# sha2017_rev0_0_1_dev.net
KiCad netlist of a schematic drawn in EAGLE
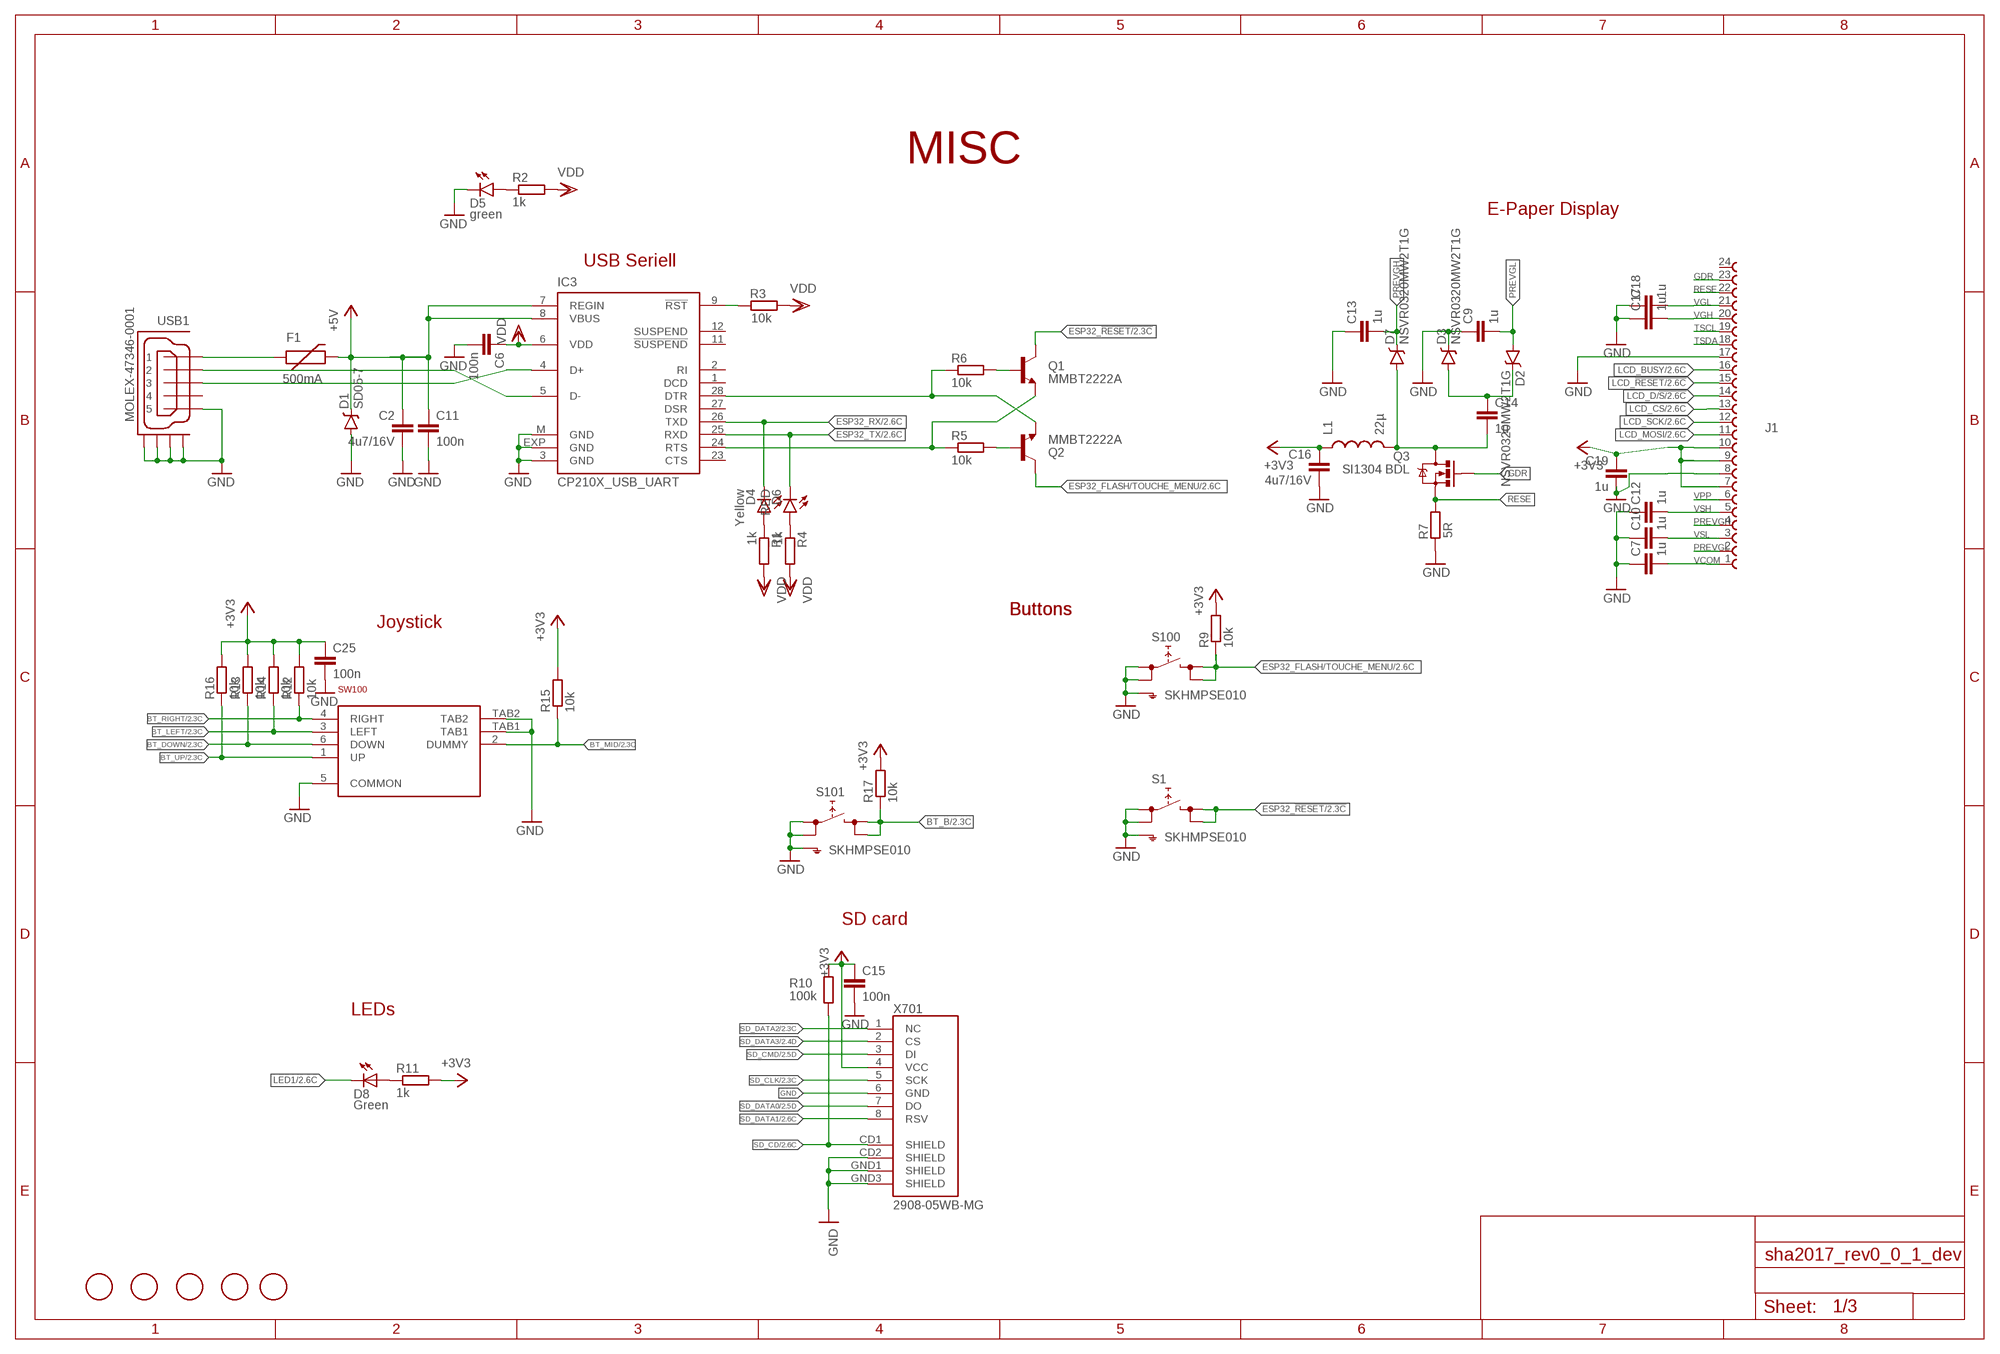
[diagram p0: schematic, sheet 1]
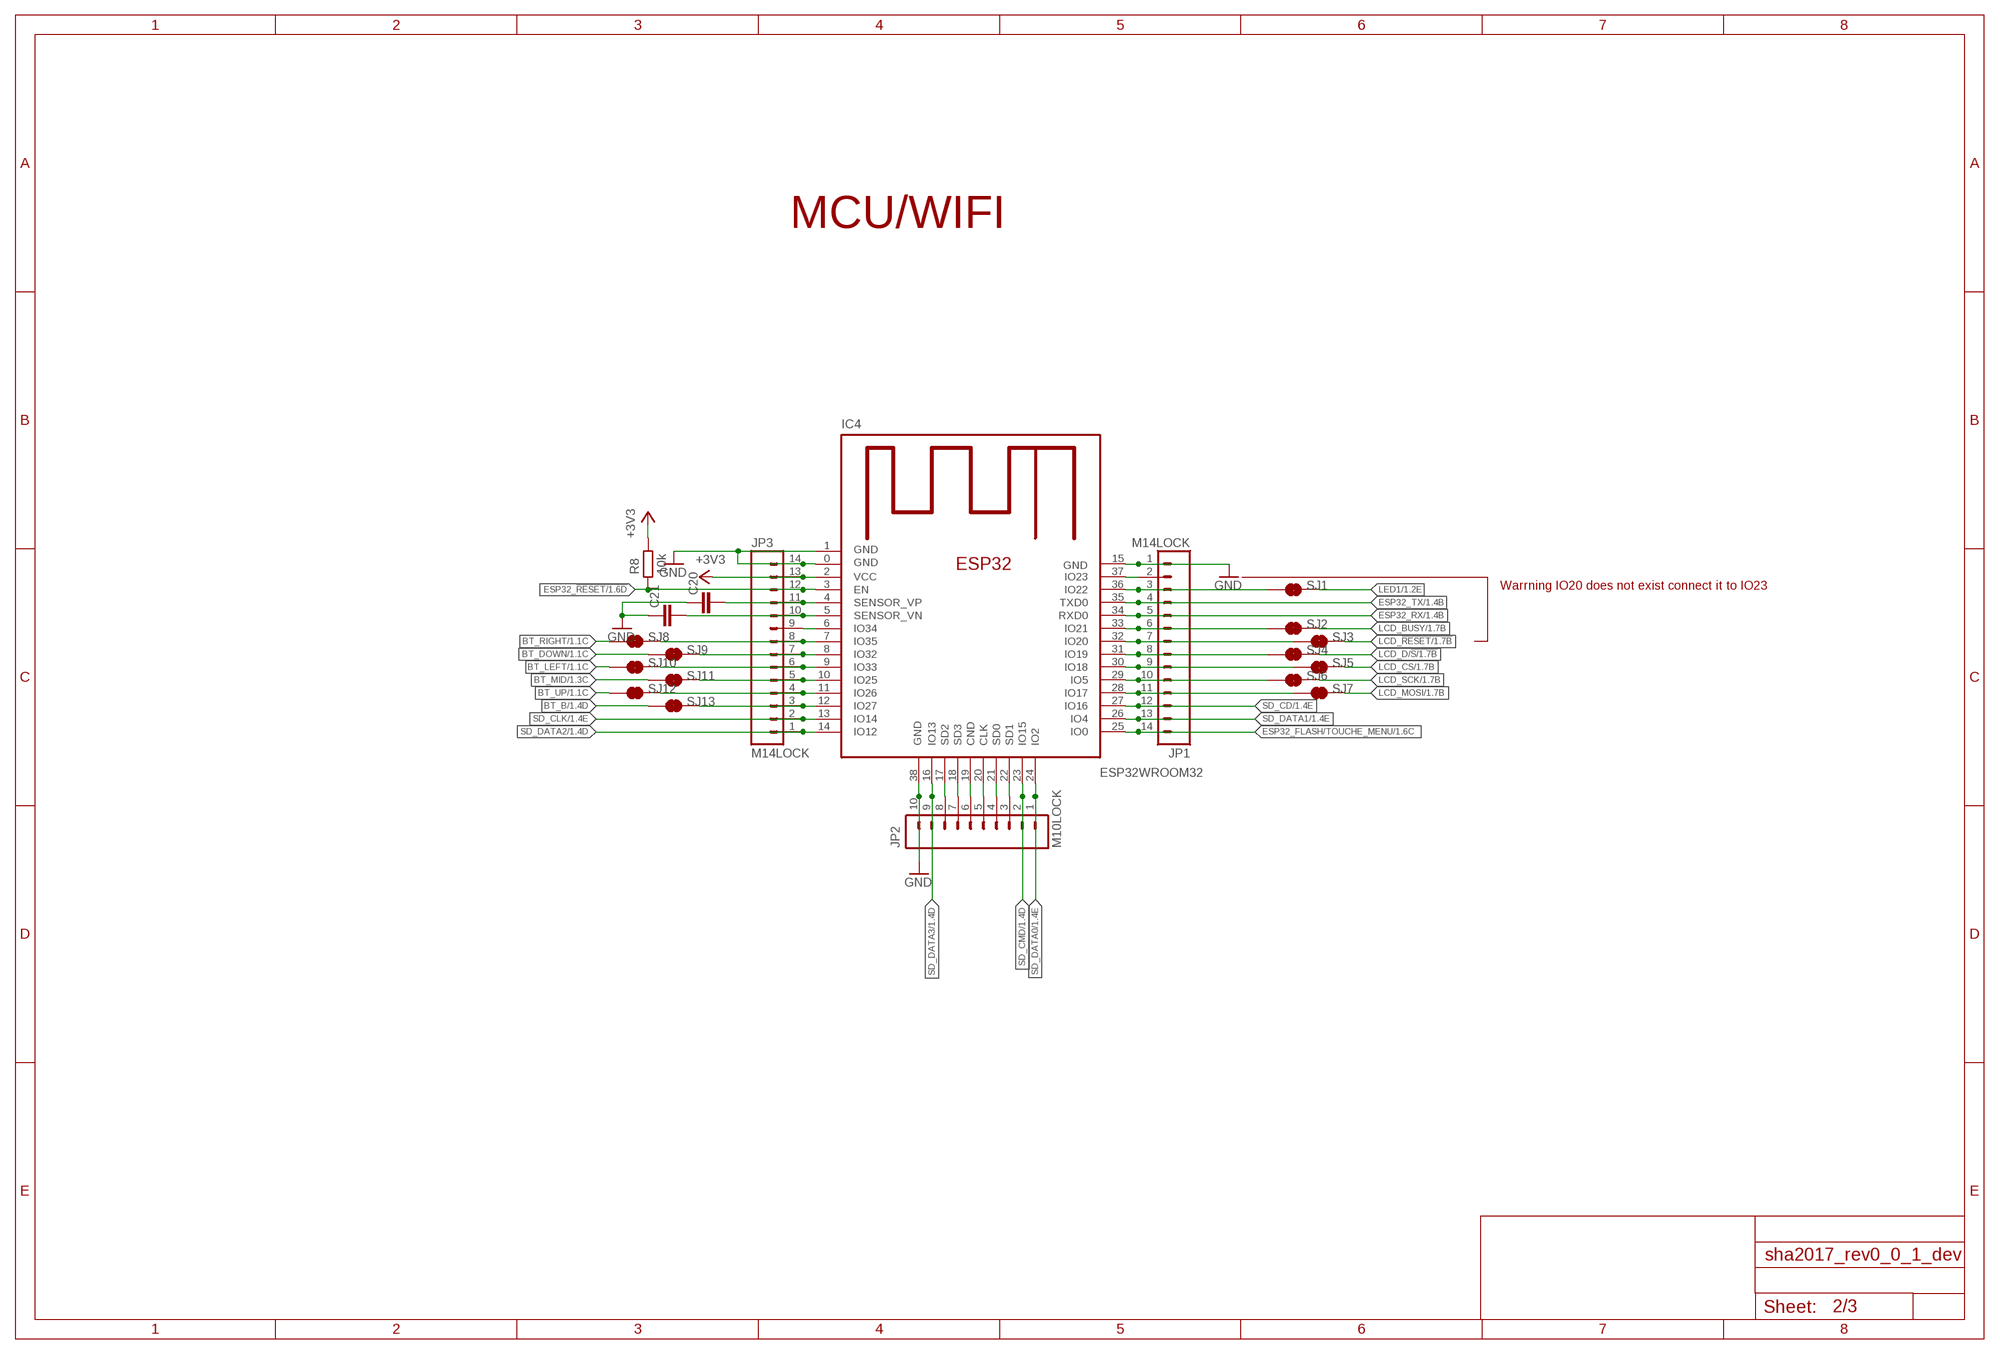
[diagram p1: schematic, sheet 2]
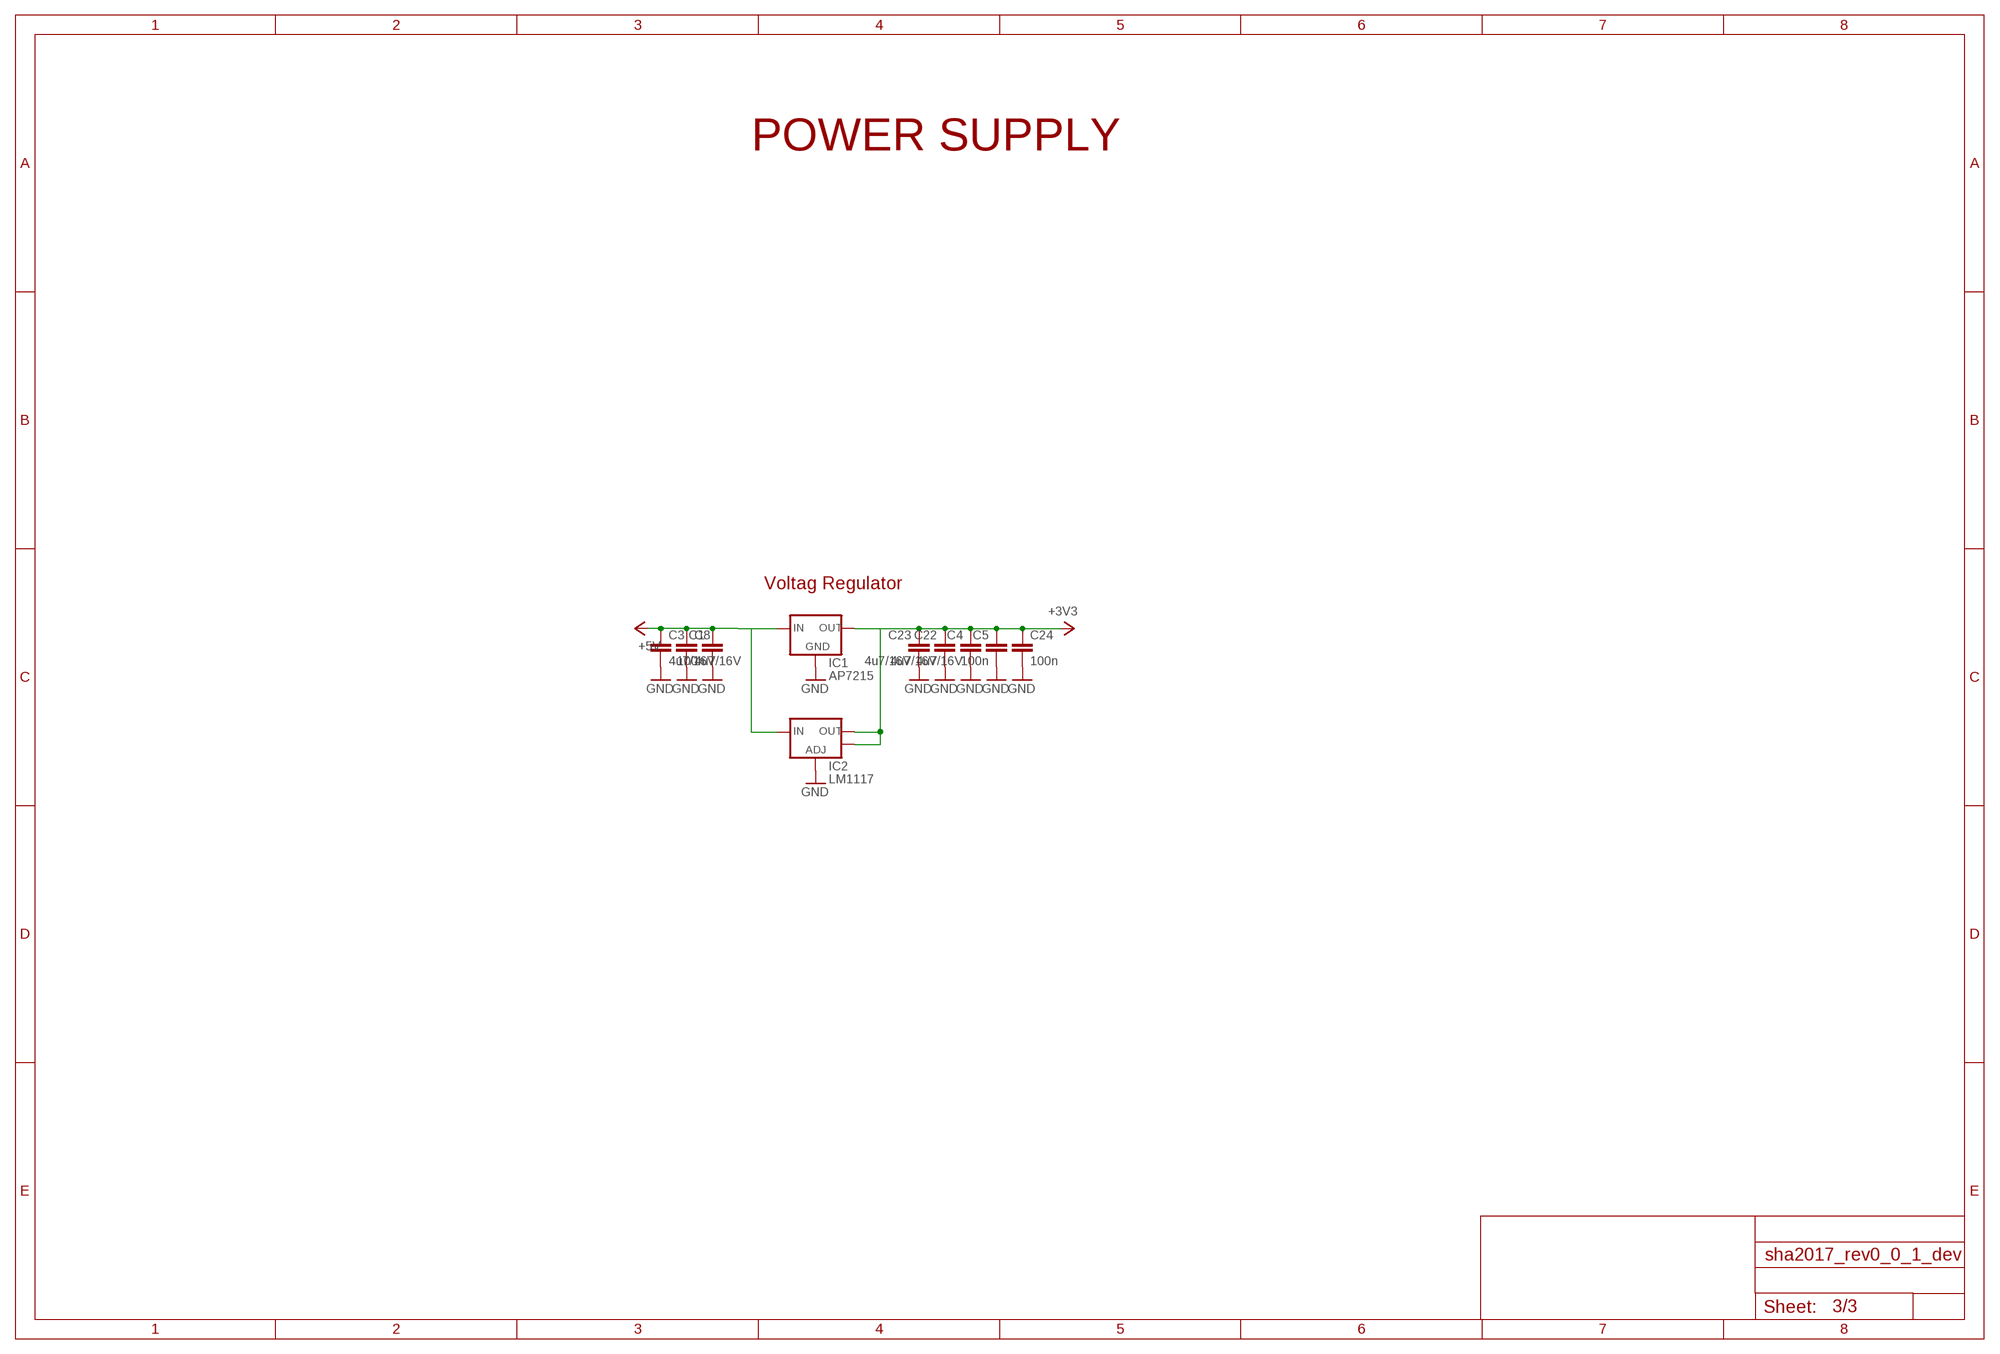
[diagram p2: schematic, sheet 3]

(export (version "E")
  (design (tool "Eeschema 10.0.6"))
  (components
    (comp (ref "C2")
      (value "4u7/16V")
      (footprint "eagle-import:C0805")
      (fields (field (name "PARTNO") "GRM21BR61C475KA88K"))
      (libsource (lib "eagle-import") (part "C-EUC0805"))
    )
    (comp (ref "C6")
      (value "100n")
      (footprint "eagle-import:C0603")
      (fields (field (name "PARTNO") "GRM188R71H104KA93D"))
      (libsource (lib "eagle-import") (part "C-EUC0603"))
    )
    (comp (ref "C7")
      (value "1u")
      (footprint "eagle-import:C0603")
      (fields (field (name "PARTNO") "GRM188R61E105KA12D"))
      (libsource (lib "eagle-import") (part "C-EUC0603"))
    )
    (comp (ref "C9")
      (value "1u")
      (footprint "eagle-import:C0603")
      (fields (field (name "PARTNO") "GRM188R61E105KA12D"))
      (libsource (lib "eagle-import") (part "C-EUC0603"))
    )
    (comp (ref "C10")
      (value "1u")
      (footprint "eagle-import:C0603")
      (fields (field (name "PARTNO") "GRM188R61E105KA12D"))
      (libsource (lib "eagle-import") (part "C-EUC0603"))
    )
    (comp (ref "C11")
      (value "100n")
      (footprint "eagle-import:C0603")
      (fields (field (name "PARTNO") "GRM188R71H104KA93D"))
      (libsource (lib "eagle-import") (part "C-EUC0603"))
    )
    (comp (ref "C12")
      (value "1u")
      (footprint "eagle-import:C0603")
      (fields (field (name "PARTNO") "GRM188R61E105KA12D"))
      (libsource (lib "eagle-import") (part "C-EUC0603"))
    )
    (comp (ref "C13")
      (value "1u")
      (footprint "eagle-import:C0603")
      (fields (field (name "PARTNO") "GRM188R61E105KA12D"))
      (libsource (lib "eagle-import") (part "C-EUC0603"))
    )
    (comp (ref "C14")
      (value "1u")
      (footprint "eagle-import:C0603")
      (fields (field (name "PARTNO") "GRM188R61E105KA12D"))
      (libsource (lib "eagle-import") (part "C-EUC0603"))
    )
    (comp (ref "C15")
      (value "100n")
      (footprint "eagle-import:C0603")
      (fields (field (name "PARTNO") "GRM188R71H104KA93D"))
      (libsource (lib "eagle-import") (part "C-EUC0603"))
    )
    (comp (ref "C16")
      (value "4u7/16V")
      (footprint "eagle-import:C0805")
      (fields (field (name "PARTNO") "GRM21BR61C475KA88K"))
      (libsource (lib "eagle-import") (part "C-EUC0805"))
    )
    (comp (ref "C17")
      (value "1u")
      (footprint "eagle-import:C0603")
      (fields (field (name "PARTNO") "GRM188R61E105KA12D"))
      (libsource (lib "eagle-import") (part "C-EUC0603"))
    )
    (comp (ref "C18")
      (value "1u")
      (footprint "eagle-import:C0603")
      (fields (field (name "PARTNO") "GRM188R61E105KA12D"))
      (libsource (lib "eagle-import") (part "C-EUC0603"))
    )
    (comp (ref "C19")
      (value "1u")
      (footprint "eagle-import:C0603")
      (fields (field (name "PARTNO") "GRM188R61E105KA12D"))
      (libsource (lib "eagle-import") (part "C-EUC0603"))
    )
    (comp (ref "C25")
      (value "100n")
      (footprint "eagle-import:C0603")
      (fields (field (name "PARTNO") "GRM188R71H104KA93D"))
      (libsource (lib "eagle-import") (part "C-EUC0603"))
    )
    (comp (ref "D1")
      (value "SD05-7")
      (footprint "eagle-import:SOD-323")
      (fields (field (name "PARTNO") "PMEG4005EJ,115"))
      (libsource (lib "eagle-import") (part "DIODE-SCHOTTKY-PMEG4005EJ"))
    )
    (comp (ref "D2")
      (value "NSVR0320MW2T1G")
      (footprint "eagle-import:SOD-323")
      (fields (field (name "PARTNO") "BAT20JFILM"))
      (libsource (lib "eagle-import") (part "BAT20JFILM"))
    )
    (comp (ref "D3")
      (value "NSVR0320MW2T1G")
      (footprint "eagle-import:SOD-323")
      (fields (field (name "PARTNO") "BAT20JFILM"))
      (libsource (lib "eagle-import") (part "BAT20JFILM"))
    )
    (comp (ref "D4")
      (value "Yellow")
      (footprint "eagle-import:LED-0603")
      (libsource (lib "eagle-import") (part "LED0603"))
    )
    (comp (ref "D5")
      (value "green")
      (footprint "eagle-import:LED-0603")
      (libsource (lib "eagle-import") (part "LED0603"))
    )
    (comp (ref "D6")
      (value "RED")
      (footprint "eagle-import:LED-0603")
      (libsource (lib "eagle-import") (part "LED0603"))
    )
    (comp (ref "D7")
      (value "NSVR0320MW2T1G")
      (footprint "eagle-import:SOD-323")
      (fields (field (name "PARTNO") "BAT20JFILM"))
      (libsource (lib "eagle-import") (part "BAT20JFILM"))
    )
    (comp (ref "D8")
      (value "Green")
      (footprint "eagle-import:SML1206")
      (fields (field (name "PARTNO") "156120VS75300"))
      (libsource (lib "eagle-import") (part "LEDSML1206"))
    )
    (comp (ref "F1")
      (value "500mA")
      (footprint "eagle-import:PTC-1206")
      (fields (field (name "PARTNO") "0ZCJ0025FF2E"))
      (libsource (lib "eagle-import") (part "PTCSMD"))
    )
    (comp (ref "FD1")
      (value "FIDUCIAL")
      (footprint "eagle-import:FIDUCIAL_1MM")
      (libsource (lib "eagle-import") (part "FIDUCIAL"))
    )
    (comp (ref "FD2")
      (value "FIDUCIAL")
      (footprint "eagle-import:FIDUCIAL_1MM")
      (libsource (lib "eagle-import") (part "FIDUCIAL"))
    )
    (comp (ref "FD3")
      (value "FIDUCIAL")
      (footprint "eagle-import:FIDUCIAL_1MM")
      (libsource (lib "eagle-import") (part "FIDUCIAL"))
    )
    (comp (ref "FD4")
      (value "FIDUCIAL")
      (footprint "eagle-import:FIDUCIAL_1MM")
      (libsource (lib "eagle-import") (part "FIDUCIAL"))
    )
    (comp (ref "FD5")
      (value "FIDUCIAL")
      (footprint "eagle-import:FIDUCIAL_1MM")
      (libsource (lib "eagle-import") (part "FIDUCIAL"))
    )
    (comp (ref "IC3")
      (value "CP210X_USB_UART")
      (footprint "eagle-import:MLP28")
      (fields (field (name "PARTNO") "CP2102-GMR"))
      (libsource (lib "eagle-import") (part "CP210X_USB_UART"))
    )
    (comp (ref "J1")
      (value "68712414022")
      (footprint "eagle-import:68712414022")
      (libsource (lib "eagle-import") (part "68712414022"))
    )
    (comp (ref "L1")
      (value "22µ")
      (footprint "eagle-import:1210")
      (fields (field (name "PARTNO") "NLCV32T-220K-EF"))
      (libsource (lib "eagle-import") (part "INDUCTOR1210"))
    )
    (comp (ref "Q1")
      (value "MMBT2222A")
      (footprint "eagle-import:SOT23-3")
      (fields (field (name "PARTNO") "BC817-25,215"))
      (libsource (lib "eagle-import") (part "TRANSISTOR_NPNMMBT2222A"))
    )
    (comp (ref "Q2")
      (value "MMBT2222A")
      (footprint "eagle-import:SOT23-3")
      (fields (field (name "PARTNO") "BC817-25,215"))
      (libsource (lib "eagle-import") (part "TRANSISTOR_NPNMMBT2222A"))
    )
    (comp (ref "Q3")
      (value "SI1304 BDL")
      (footprint "eagle-import:SOT323")
      (fields (field (name "PARTNO") "SI1308EDL-T1-GE3"))
      (libsource (lib "eagle-import") (part "MOSFET-NCHANNEL2N7002PW"))
    )
    (comp (ref "R1")
      (value "1k")
      (footprint "eagle-import:R0603")
      (fields (field (name "PARTNO") "ERJ-3GEYJ102V"))
      (libsource (lib "eagle-import") (part "R-EU_R0603"))
    )
    (comp (ref "R2")
      (value "1k")
      (footprint "eagle-import:R0603")
      (fields (field (name "PARTNO") "ERJ-3GEYJ102V"))
      (libsource (lib "eagle-import") (part "R-EU_R0603"))
    )
    (comp (ref "R3")
      (value "10k")
      (footprint "eagle-import:R0603")
      (fields (field (name "PARTNO") "ERJ-3GEYJ103V"))
      (libsource (lib "eagle-import") (part "R-EU_R0603"))
    )
    (comp (ref "R4")
      (value "1k")
      (footprint "eagle-import:R0603")
      (fields (field (name "PARTNO") "ERJ-3GEYJ102V"))
      (libsource (lib "eagle-import") (part "R-EU_R0603"))
    )
    (comp (ref "R5")
      (value "10k")
      (footprint "eagle-import:R0603")
      (fields (field (name "PARTNO") "ERJ-3GEYJ103V"))
      (libsource (lib "eagle-import") (part "R-EU_R0603"))
    )
    (comp (ref "R6")
      (value "10k")
      (footprint "eagle-import:R0603")
      (fields (field (name "PARTNO") "ERJ-3GEYJ103V"))
      (libsource (lib "eagle-import") (part "R-EU_R0603"))
    )
    (comp (ref "R7")
      (value "5R")
      (footprint "eagle-import:R0603-DASHES")
      (fields (field (name "PARTNO") "ERJ-3GEYJ5R1V"))
      (libsource (lib "eagle-import") (part "R0603-DASHES"))
    )
    (comp (ref "R9")
      (value "10k")
      (footprint "eagle-import:R0603")
      (fields (field (name "PARTNO") "ERJ-3GEYJ103V"))
      (libsource (lib "eagle-import") (part "R-EU_R0603"))
    )
    (comp (ref "R10")
      (value "100k")
      (footprint "eagle-import:R0603")
      (fields (field (name "PARTNO") "CRCW0603100KFKEA"))
      (libsource (lib "eagle-import") (part "R-EU_R0603"))
    )
    (comp (ref "R11")
      (value "1k")
      (footprint "eagle-import:R0603")
      (fields (field (name "PARTNO") "ERJ-3GEYJ102V"))
      (libsource (lib "eagle-import") (part "R-EU_R0603"))
    )
    (comp (ref "R12")
      (value "10k")
      (footprint "eagle-import:R0603")
      (fields (field (name "PARTNO") "ERJ-3GEYJ103V"))
      (libsource (lib "eagle-import") (part "R-EU_R0603"))
    )
    (comp (ref "R13")
      (value "10k")
      (footprint "eagle-import:R0603")
      (fields (field (name "PARTNO") "ERJ-3GEYJ103V"))
      (libsource (lib "eagle-import") (part "R-EU_R0603"))
    )
    (comp (ref "R14")
      (value "10k")
      (footprint "eagle-import:R0603")
      (fields (field (name "PARTNO") "ERJ-3GEYJ103V"))
      (libsource (lib "eagle-import") (part "R-EU_R0603"))
    )
    (comp (ref "R15")
      (value "10k")
      (footprint "eagle-import:R0603")
      (fields (field (name "PARTNO") "ERJ-3GEYJ103V"))
      (libsource (lib "eagle-import") (part "R-EU_R0603"))
    )
    (comp (ref "R16")
      (value "10k")
      (footprint "eagle-import:R0603")
      (fields (field (name "PARTNO") "ERJ-3GEYJ103V"))
      (libsource (lib "eagle-import") (part "R-EU_R0603"))
    )
    (comp (ref "R17")
      (value "10k")
      (footprint "eagle-import:R0603")
      (fields (field (name "PARTNO") "ERJ-3GEYJ103V"))
      (libsource (lib "eagle-import") (part "R-EU_R0603"))
    )
    (comp (ref "S1")
      (value "SKHMPSE010")
      (footprint "eagle-import:SKHMPXE010")
      (fields (field (name "PARTNO") "SKHMQME010"))
      (libsource (lib "eagle-import") (part "SKHMPE010S"))
    )
    (comp (ref "S100")
      (value "SKHMPSE010")
      (footprint "eagle-import:SKHMPXE010")
      (fields (field (name "PARTNO") "SKHMQME010"))
      (libsource (lib "eagle-import") (part "SKHMPE010S"))
    )
    (comp (ref "S101")
      (value "SKHMPSE010")
      (footprint "eagle-import:SKHMPXE010")
      (fields (field (name "PARTNO") "SKHMQME010"))
      (libsource (lib "eagle-import") (part "SKHMPE010S"))
    )
    (comp (ref "SW100")
      (value "MCMT5-F-V")
      (footprint "eagle-import:MCMT5-F-V")
      (fields (field (name "PARTNO") "SKRHAAE010"))
      (libsource (lib "eagle-import") (part "MCMT5-F-V"))
    )
    (comp (ref "USB1")
      (value "MOLEX-47346-0001")
      (footprint "eagle-import:MOLEX-47364-0001")
      (fields (field (name "PARTNO") "10118194-0001LF"))
      (libsource (lib "eagle-import") (part "MOLEX-47346-0001"))
    )
    (comp (ref "X701")
      (value "2908-05WB-MG")
      (footprint "eagle-import:MICRO-SD-SOCKET-PP")
      (libsource (lib "eagle-import") (part "2908-05WB-MG"))
    )
    (comp (ref "C1")
      (value "100n")
      (footprint "eagle-import:C0603")
      (fields (field (name "PARTNO") "GRM188R71H104KA93D"))
      (libsource (lib "eagle-import") (part "C-EUC0603"))
    )
    (comp (ref "C3")
      (value "4u7/16V")
      (footprint "eagle-import:C0805")
      (fields (field (name "PARTNO") "GRM21BR61C475KA88K"))
      (libsource (lib "eagle-import") (part "C-EUC0805"))
    )
    (comp (ref "C4")
      (value "4u7/16V")
      (footprint "eagle-import:C0805")
      (fields (field (name "PARTNO") "GRM21BR61C475KA88K"))
      (libsource (lib "eagle-import") (part "C-EUC0805"))
    )
    (comp (ref "C5")
      (value "100n")
      (footprint "eagle-import:C0603")
      (fields (field (name "PARTNO") "GRM188R71H104KA93D"))
      (libsource (lib "eagle-import") (part "C-EUC0603"))
    )
    (comp (ref "C8")
      (value "4u7/16V")
      (footprint "eagle-import:C0805")
      (fields (field (name "PARTNO") "GRM21BR61C475KA88K"))
      (libsource (lib "eagle-import") (part "C-EUC0805"))
    )
    (comp (ref "C22")
      (value "4u7/16V")
      (footprint "eagle-import:C0805")
      (fields (field (name "PARTNO") "GRM21BR61C475KA88K"))
      (libsource (lib "eagle-import") (part "C-EUC0805"))
    )
    (comp (ref "C23")
      (value "4u7/16V")
      (footprint "eagle-import:C0805")
      (fields (field (name "PARTNO") "GRM21BR61C475KA88K"))
      (libsource (lib "eagle-import") (part "C-EUC0805"))
    )
    (comp (ref "C24")
      (value "100n")
      (footprint "eagle-import:C0603")
      (fields (field (name "PARTNO") "GRM188R71H104KA93D"))
      (libsource (lib "eagle-import") (part "C-EUC0603"))
    )
    (comp (ref "IC1")
      (value "AP7215")
      (footprint "eagle-import:SOT89")
      (fields (field (name "PARTNO") "AP7215-33YG-13"))
      (libsource (lib "eagle-import") (part "AP7215"))
    )
    (comp (ref "IC2")
      (value "LM1117")
      (footprint "eagle-import:SOT223")
      (fields (field (name "PARTNO") "LM1117MPX-3.3/NOPB"))
      (libsource (lib "eagle-import") (part "V_REG_LM1117SOT223"))
    )
    (comp (ref "C20")
      (value "C-EUC0603")
      (footprint "eagle-import:C0603")
      (libsource (lib "eagle-import") (part "C-EUC0603"))
    )
    (comp (ref "C21")
      (value "C-EUC0603")
      (footprint "eagle-import:C0603")
      (libsource (lib "eagle-import") (part "C-EUC0603"))
    )
    (comp (ref "IC4")
      (value "ESP32WROOM32")
      (footprint "eagle-import:ESP32MOD")
      (libsource (lib "eagle-import") (part "ESP32WROOM32"))
    )
    (comp (ref "JP1")
      (value "M14LOCK")
      (footprint "eagle-import:1X14_LOCK")
      (libsource (lib "eagle-import") (part "M14LOCK"))
    )
    (comp (ref "JP2")
      (value "M10LOCK")
      (footprint "eagle-import:1X10_LOCK")
      (libsource (lib "eagle-import") (part "M10LOCK"))
    )
    (comp (ref "JP3")
      (value "M14LOCK")
      (footprint "eagle-import:1X14_LOCK")
      (libsource (lib "eagle-import") (part "M14LOCK"))
    )
    (comp (ref "R8")
      (value "10k")
      (footprint "eagle-import:R0603")
      (fields (field (name "PARTNO") "ERJ-3GEYJ103V"))
      (libsource (lib "eagle-import") (part "R-EU_R0603"))
    )
    (comp (ref "SJ1")
      (value "JUMPER-PAD-2-NC_BY_TRACE")
      (footprint "eagle-import:PAD-JUMPER-2-NC_BY_TRACE_YES_SILK")
      (libsource (lib "eagle-import") (part "JUMPER-PAD-2-NC_BY_TRACE"))
    )
    (comp (ref "SJ2")
      (value "JUMPER-PAD-2-NC_BY_TRACE")
      (footprint "eagle-import:PAD-JUMPER-2-NC_BY_TRACE_YES_SILK")
      (libsource (lib "eagle-import") (part "JUMPER-PAD-2-NC_BY_TRACE"))
    )
    (comp (ref "SJ3")
      (value "JUMPER-PAD-2-NC_BY_TRACE")
      (footprint "eagle-import:PAD-JUMPER-2-NC_BY_TRACE_YES_SILK")
      (libsource (lib "eagle-import") (part "JUMPER-PAD-2-NC_BY_TRACE"))
    )
    (comp (ref "SJ4")
      (value "JUMPER-PAD-2-NC_BY_TRACE")
      (footprint "eagle-import:PAD-JUMPER-2-NC_BY_TRACE_YES_SILK")
      (libsource (lib "eagle-import") (part "JUMPER-PAD-2-NC_BY_TRACE"))
    )
    (comp (ref "SJ5")
      (value "JUMPER-PAD-2-NC_BY_TRACE")
      (footprint "eagle-import:PAD-JUMPER-2-NC_BY_TRACE_YES_SILK")
      (libsource (lib "eagle-import") (part "JUMPER-PAD-2-NC_BY_TRACE"))
    )
    (comp (ref "SJ6")
      (value "JUMPER-PAD-2-NC_BY_TRACE")
      (footprint "eagle-import:PAD-JUMPER-2-NC_BY_TRACE_YES_SILK")
      (libsource (lib "eagle-import") (part "JUMPER-PAD-2-NC_BY_TRACE"))
    )
    (comp (ref "SJ7")
      (value "JUMPER-PAD-2-NC_BY_TRACE")
      (footprint "eagle-import:PAD-JUMPER-2-NC_BY_TRACE_YES_SILK")
      (libsource (lib "eagle-import") (part "JUMPER-PAD-2-NC_BY_TRACE"))
    )
    (comp (ref "SJ8")
      (value "JUMPER-PAD-2-NC_BY_TRACE")
      (footprint "eagle-import:PAD-JUMPER-2-NC_BY_TRACE_YES_SILK")
      (libsource (lib "eagle-import") (part "JUMPER-PAD-2-NC_BY_TRACE"))
    )
    (comp (ref "SJ9")
      (value "JUMPER-PAD-2-NC_BY_TRACE")
      (footprint "eagle-import:PAD-JUMPER-2-NC_BY_TRACE_YES_SILK")
      (libsource (lib "eagle-import") (part "JUMPER-PAD-2-NC_BY_TRACE"))
    )
    (comp (ref "SJ10")
      (value "JUMPER-PAD-2-NC_BY_TRACE")
      (footprint "eagle-import:PAD-JUMPER-2-NC_BY_TRACE_YES_SILK")
      (libsource (lib "eagle-import") (part "JUMPER-PAD-2-NC_BY_TRACE"))
    )
    (comp (ref "SJ11")
      (value "JUMPER-PAD-2-NC_BY_TRACE")
      (footprint "eagle-import:PAD-JUMPER-2-NC_BY_TRACE_YES_SILK")
      (libsource (lib "eagle-import") (part "JUMPER-PAD-2-NC_BY_TRACE"))
    )
    (comp (ref "SJ12")
      (value "JUMPER-PAD-2-NC_BY_TRACE")
      (footprint "eagle-import:PAD-JUMPER-2-NC_BY_TRACE_YES_SILK")
      (libsource (lib "eagle-import") (part "JUMPER-PAD-2-NC_BY_TRACE"))
    )
    (comp (ref "SJ13")
      (value "JUMPER-PAD-2-NC_BY_TRACE")
      (footprint "eagle-import:PAD-JUMPER-2-NC_BY_TRACE_YES_SILK")
      (libsource (lib "eagle-import") (part "JUMPER-PAD-2-NC_BY_TRACE"))
    )
  )
  (nets
    (net (code "1") (name "+3V3") (class "Default")
      (node (ref "C15") (pin "1") (pinfunction "1_1") (pintype "passive"))
      (node (ref "C16") (pin "1") (pinfunction "1_1") (pintype "passive"))
      (node (ref "C19") (pin "1") (pinfunction "1_1") (pintype "passive"))
      (node (ref "C22") (pin "1") (pinfunction "1_1") (pintype "passive"))
      (node (ref "C23") (pin "1") (pinfunction "1_1") (pintype "passive"))
      (node (ref "C24") (pin "1") (pinfunction "1_1") (pintype "passive"))
      (node (ref "C25") (pin "1") (pinfunction "1_1") (pintype "passive"))
      (node (ref "C4") (pin "1") (pinfunction "1_1") (pintype "passive"))
      (node (ref "C5") (pin "1") (pinfunction "1_1") (pintype "passive"))
      (node (ref "IC1") (pin "3") (pinfunction "OUT_3") (pintype "passive"))
      (node (ref "IC2") (pin "2") (pinfunction "OUT_2") (pintype "output"))
      (node (ref "IC2") (pin "4") (pinfunction "OUT_4") (pintype "output"))
      (node (ref "IC4") (pin "2") (pinfunction "VCC_2") (pintype "power_in"))
      (node (ref "J1") (pin "10") (pinfunction "10_10") (pintype "passive"))
      (node (ref "J1") (pin "7") (pinfunction "7_7") (pintype "passive"))
      (node (ref "J1") (pin "9") (pinfunction "9_9") (pintype "passive"))
      (node (ref "JP3") (pin "13") (pinfunction "13_13") (pintype "passive"))
      (node (ref "L1") (pin "1") (pinfunction "1_1") (pintype "passive"))
      (node (ref "R10") (pin "1") (pinfunction "1_1") (pintype "passive"))
      (node (ref "R11") (pin "2") (pinfunction "2_2") (pintype "passive"))
      (node (ref "R12") (pin "2") (pinfunction "2_2") (pintype "passive"))
      (node (ref "R13") (pin "2") (pinfunction "2_2") (pintype "passive"))
      (node (ref "R14") (pin "2") (pinfunction "2_2") (pintype "passive"))
      (node (ref "R15") (pin "2") (pinfunction "2_2") (pintype "passive"))
      (node (ref "R16") (pin "2") (pinfunction "2_2") (pintype "passive"))
      (node (ref "R17") (pin "2") (pinfunction "2_2") (pintype "passive"))
      (node (ref "R8") (pin "1") (pinfunction "1_1") (pintype "passive"))
      (node (ref "R9") (pin "2") (pinfunction "2_2") (pintype "passive"))
      (node (ref "X701") (pin "4") (pinfunction "VCC_4") (pintype "bidirectional"))
    )
    (net (code "2") (name "+5V") (class "Default")
      (node (ref "C1") (pin "1") (pinfunction "1_1") (pintype "passive"))
      (node (ref "C11") (pin "1") (pinfunction "1_1") (pintype "passive"))
      (node (ref "C2") (pin "1") (pinfunction "1_1") (pintype "passive"))
      (node (ref "C3") (pin "1") (pinfunction "1_1") (pintype "passive"))
      (node (ref "C8") (pin "1") (pinfunction "1_1") (pintype "passive"))
      (node (ref "D1") (pin "C") (pinfunction "C_C") (pintype "passive"))
      (node (ref "F1") (pin "2") (pinfunction "2_2") (pintype "bidirectional"))
      (node (ref "IC1") (pin "2") (pinfunction "IN_2") (pintype "input"))
      (node (ref "IC1") (pin "2@") (pinfunction "IN_2@") (pintype "input"))
      (node (ref "IC2") (pin "3") (pinfunction "IN_3") (pintype "input"))
      (node (ref "IC3") (pin "7") (pinfunction "REGIN_7") (pintype "passive"))
      (node (ref "IC3") (pin "8") (pinfunction "VBUS_8") (pintype "input"))
    )
    (net (code "3") (name "BT_B") (class "Default")
      (node (ref "R17") (pin "1") (pinfunction "1_1") (pintype "passive"))
      (node (ref "S101") (pin "3") (pinfunction "2.1_3") (pintype "passive"))
      (node (ref "S101") (pin "4") (pinfunction "2.2_4") (pintype "passive"))
      (node (ref "SJ13") (pin "1") (pinfunction "1_1") (pintype "passive"))
    )
    (net (code "4") (name "BT_DOWN") (class "Default")
      (node (ref "R13") (pin "1") (pinfunction "1_1") (pintype "passive"))
      (node (ref "SJ9") (pin "1") (pinfunction "1_1") (pintype "passive"))
      (node (ref "SW100") (pin "6") (pinfunction "DOWN_6") (pintype "bidirectional"))
    )
    (net (code "5") (name "BT_LEFT") (class "Default")
      (node (ref "R14") (pin "1") (pinfunction "1_1") (pintype "passive"))
      (node (ref "SJ10") (pin "1") (pinfunction "1_1") (pintype "passive"))
      (node (ref "SW100") (pin "3") (pinfunction "LEFT_3") (pintype "bidirectional"))
    )
    (net (code "6") (name "BT_MID") (class "Default")
      (node (ref "R15") (pin "1") (pinfunction "1_1") (pintype "passive"))
      (node (ref "SJ11") (pin "1") (pinfunction "1_1") (pintype "passive"))
      (node (ref "SW100") (pin "2") (pinfunction "DUMMY_2") (pintype "bidirectional"))
    )
    (net (code "7") (name "BT_RIGHT") (class "Default")
      (node (ref "R12") (pin "1") (pinfunction "1_1") (pintype "passive"))
      (node (ref "SJ8") (pin "1") (pinfunction "1_1") (pintype "passive"))
      (node (ref "SW100") (pin "4") (pinfunction "RIGHT_4") (pintype "bidirectional"))
    )
    (net (code "8") (name "BT_UP") (class "Default")
      (node (ref "R16") (pin "1") (pinfunction "1_1") (pintype "passive"))
      (node (ref "SJ12") (pin "1") (pinfunction "1_1") (pintype "passive"))
      (node (ref "SW100") (pin "1") (pinfunction "UP_1") (pintype "bidirectional"))
    )
    (net (code "9") (name "ESP32_FLASH{slash}TOUCHE_MENU") (class "Default")
      (node (ref "IC4") (pin "25") (pinfunction "IO0_25") (pintype "bidirectional"))
      (node (ref "JP1") (pin "14") (pinfunction "14_14") (pintype "passive"))
      (node (ref "Q2") (pin "3") (pinfunction "C_3") (pintype "passive"))
      (node (ref "R9") (pin "1") (pinfunction "1_1") (pintype "passive"))
      (node (ref "S100") (pin "3") (pinfunction "2.1_3") (pintype "passive"))
      (node (ref "S100") (pin "4") (pinfunction "2.2_4") (pintype "passive"))
    )
    (net (code "10") (name "ESP32_RX") (class "Default")
      (node (ref "D4") (pin "C") (pinfunction "C_C") (pintype "passive"))
      (node (ref "IC3") (pin "26") (pinfunction "TXD_26") (pintype "output"))
      (node (ref "IC4") (pin "34") (pinfunction "RXD0_34") (pintype "bidirectional"))
      (node (ref "JP1") (pin "5") (pinfunction "5_5") (pintype "passive"))
    )
    (net (code "11") (name "ESP32_TX") (class "Default")
      (node (ref "D6") (pin "C") (pinfunction "C_C") (pintype "passive"))
      (node (ref "IC3") (pin "25") (pinfunction "RXD_25") (pintype "input"))
      (node (ref "IC4") (pin "35") (pinfunction "TXD0_35") (pintype "bidirectional"))
      (node (ref "JP1") (pin "4") (pinfunction "4_4") (pintype "passive"))
    )
    (net (code "12") (name "ESP32_~{RESET}") (class "Default")
      (node (ref "IC4") (pin "3") (pinfunction "EN_3") (pintype "bidirectional"))
      (node (ref "JP3") (pin "12") (pinfunction "12_12") (pintype "passive"))
      (node (ref "Q1") (pin "3") (pinfunction "C_3") (pintype "passive"))
      (node (ref "R8") (pin "2") (pinfunction "2_2") (pintype "passive"))
      (node (ref "S1") (pin "3") (pinfunction "2.1_3") (pintype "passive"))
      (node (ref "S1") (pin "4") (pinfunction "2.2_4") (pintype "passive"))
    )
    (net (code "13") (name "GDR") (class "Default")
      (node (ref "J1") (pin "23") (pinfunction "23_23") (pintype "passive"))
      (node (ref "Q3") (pin "1") (pinfunction "G_1") (pintype "passive"))
    )
    (net (code "14") (name "GND") (class "Default")
      (node (ref "C1") (pin "2") (pinfunction "2_2") (pintype "passive"))
      (node (ref "C10") (pin "1") (pinfunction "1_1") (pintype "passive"))
      (node (ref "C11") (pin "2") (pinfunction "2_2") (pintype "passive"))
      (node (ref "C12") (pin "1") (pinfunction "1_1") (pintype "passive"))
      (node (ref "C13") (pin "1") (pinfunction "1_1") (pintype "passive"))
      (node (ref "C15") (pin "2") (pinfunction "2_2") (pintype "passive"))
      (node (ref "C16") (pin "2") (pinfunction "2_2") (pintype "passive"))
      (node (ref "C17") (pin "1") (pinfunction "1_1") (pintype "passive"))
      (node (ref "C18") (pin "1") (pinfunction "1_1") (pintype "passive"))
      (node (ref "C19") (pin "2") (pinfunction "2_2") (pintype "passive"))
      (node (ref "C2") (pin "2") (pinfunction "2_2") (pintype "passive"))
      (node (ref "C20") (pin "1") (pinfunction "1_1") (pintype "passive"))
      (node (ref "C21") (pin "1") (pinfunction "1_1") (pintype "passive"))
      (node (ref "C22") (pin "2") (pinfunction "2_2") (pintype "passive"))
      (node (ref "C23") (pin "2") (pinfunction "2_2") (pintype "passive"))
      (node (ref "C24") (pin "2") (pinfunction "2_2") (pintype "passive"))
      (node (ref "C25") (pin "2") (pinfunction "2_2") (pintype "passive"))
      (node (ref "C3") (pin "2") (pinfunction "2_2") (pintype "passive"))
      (node (ref "C4") (pin "2") (pinfunction "2_2") (pintype "passive"))
      (node (ref "C5") (pin "2") (pinfunction "2_2") (pintype "passive"))
      (node (ref "C6") (pin "2") (pinfunction "2_2") (pintype "passive"))
      (node (ref "C7") (pin "1") (pinfunction "1_1") (pintype "passive"))
      (node (ref "C8") (pin "2") (pinfunction "2_2") (pintype "passive"))
      (node (ref "C9") (pin "1") (pinfunction "1_1") (pintype "passive"))
      (node (ref "D1") (pin "A") (pinfunction "A_A") (pintype "passive"))
      (node (ref "D3") (pin "C") (pinfunction "C_C") (pintype "passive"))
      (node (ref "D5") (pin "C") (pinfunction "C_C") (pintype "passive"))
      (node (ref "IC1") (pin "1") (pinfunction "GND_1") (pintype "input"))
      (node (ref "IC2") (pin "1") (pinfunction "ADJ_1") (pintype "input"))
      (node (ref "IC3") (pin "3") (pinfunction "GND_3") (pintype "power_in"))
      (node (ref "IC3") (pin "EXP") (pinfunction "GND_EXP") (pintype "power_in"))
      (node (ref "IC3") (pin "M") (pinfunction "GND_M") (pintype "power_in"))
      (node (ref "IC4") (pin "0") (pinfunction "GND_0") (pintype "power_in"))
      (node (ref "IC4") (pin "1") (pinfunction "GND_1") (pintype "power_in"))
      (node (ref "IC4") (pin "15") (pinfunction "GND_15") (pintype "power_in"))
      (node (ref "IC4") (pin "38") (pinfunction "GND_38") (pintype "power_in"))
      (node (ref "J1") (pin "17") (pinfunction "17_17") (pintype "passive"))
      (node (ref "J1") (pin "8") (pinfunction "8_8") (pintype "passive"))
      (node (ref "JP1") (pin "1") (pinfunction "1_1") (pintype "passive"))
      (node (ref "JP2") (pin "10") (pinfunction "10_10") (pintype "passive"))
      (node (ref "JP3") (pin "14") (pinfunction "14_14") (pintype "passive"))
      (node (ref "R7") (pin "2") (pinfunction "2_2") (pintype "passive"))
      (node (ref "S1") (pin "1") (pinfunction "1.1_1") (pintype "passive"))
      (node (ref "S1") (pin "2") (pinfunction "1.2_2") (pintype "passive"))
      (node (ref "S1") (pin "5") (pinfunction "SH_5") (pintype "passive"))
      (node (ref "S100") (pin "1") (pinfunction "1.1_1") (pintype "passive"))
      (node (ref "S100") (pin "2") (pinfunction "1.2_2") (pintype "passive"))
      (node (ref "S100") (pin "5") (pinfunction "SH_5") (pintype "passive"))
      (node (ref "S101") (pin "1") (pinfunction "1.1_1") (pintype "passive"))
      (node (ref "S101") (pin "2") (pinfunction "1.2_2") (pintype "passive"))
      (node (ref "S101") (pin "5") (pinfunction "SH_5") (pintype "passive"))
      (node (ref "SW100") (pin "5") (pinfunction "COMMON_5") (pintype "bidirectional"))
      (node (ref "SW100") (pin "TAB1") (pinfunction "TAB1_TAB1") (pintype "bidirectional"))
      (node (ref "SW100") (pin "TAB2") (pinfunction "TAB2_TAB2") (pintype "bidirectional"))
      (node (ref "USB1") (pin "5") (pinfunction "5_5") (pintype "input"))
      (node (ref "USB1") (pin "GND1") (pinfunction "GND1_GND1") (pintype "bidirectional"))
      (node (ref "USB1") (pin "GND2") (pinfunction "GND2_GND2") (pintype "bidirectional"))
      (node (ref "USB1") (pin "GND3") (pinfunction "GND3_GND3") (pintype "bidirectional"))
      (node (ref "USB1") (pin "GND4") (pinfunction "GND4_GND4") (pintype "bidirectional"))
      (node (ref "X701") (pin "6") (pinfunction "GND_6") (pintype "bidirectional"))
      (node (ref "X701") (pin "CD2") (pinfunction "SHIELD_CD2") (pintype "bidirectional"))
      (node (ref "X701") (pin "GND1") (pinfunction "SHIELD_GND1") (pintype "bidirectional"))
      (node (ref "X701") (pin "GND3") (pinfunction "SHIELD_GND3") (pintype "bidirectional"))
    )
    (net (code "15") (name "LCD_BUSY") (class "Default")
      (node (ref "J1") (pin "16") (pinfunction "16_16") (pintype "passive"))
      (node (ref "SJ2") (pin "2") (pinfunction "2_2") (pintype "passive"))
    )
    (net (code "16") (name "LCD_CS") (class "Default")
      (node (ref "J1") (pin "13") (pinfunction "13_13") (pintype "passive"))
      (node (ref "SJ5") (pin "2") (pinfunction "2_2") (pintype "passive"))
    )
    (net (code "17") (name "LCD_D{slash}~{S}") (class "Default")
      (node (ref "J1") (pin "14") (pinfunction "14_14") (pintype "passive"))
      (node (ref "SJ4") (pin "2") (pinfunction "2_2") (pintype "passive"))
    )
    (net (code "18") (name "LCD_MOSI") (class "Default")
      (node (ref "J1") (pin "11") (pinfunction "11_11") (pintype "passive"))
      (node (ref "SJ7") (pin "2") (pinfunction "2_2") (pintype "passive"))
    )
    (net (code "19") (name "LCD_SCK") (class "Default")
      (node (ref "J1") (pin "12") (pinfunction "12_12") (pintype "passive"))
      (node (ref "SJ6") (pin "2") (pinfunction "2_2") (pintype "passive"))
    )
    (net (code "20") (name "LCD_~{RESET}") (class "Default")
      (node (ref "J1") (pin "15") (pinfunction "15_15") (pintype "passive"))
      (node (ref "SJ3") (pin "2") (pinfunction "2_2") (pintype "passive"))
    )
    (net (code "21") (name "LED1") (class "Default")
      (node (ref "D8") (pin "C") (pinfunction "C_C") (pintype "passive"))
      (node (ref "SJ1") (pin "2") (pinfunction "2_2") (pintype "passive"))
    )
    (net (code "22") (name "Net-(C14-Pad1)") (class "Default")
      (node (ref "C14") (pin "1") (pinfunction "1_1") (pintype "passive"))
      (node (ref "D2") (pin "C") (pinfunction "C_C") (pintype "passive"))
      (node (ref "D3") (pin "A") (pinfunction "A_A") (pintype "passive"))
    )
    (net (code "23") (name "Net-(D4-PadA)") (class "Default")
      (node (ref "D4") (pin "A") (pinfunction "A_A") (pintype "passive"))
      (node (ref "R1") (pin "1") (pinfunction "1_1") (pintype "passive"))
    )
    (net (code "24") (name "Net-(D5-PadA)") (class "Default")
      (node (ref "D5") (pin "A") (pinfunction "A_A") (pintype "passive"))
      (node (ref "R2") (pin "1") (pinfunction "1_1") (pintype "passive"))
    )
    (net (code "25") (name "Net-(D6-PadA)") (class "Default")
      (node (ref "D6") (pin "A") (pinfunction "A_A") (pintype "passive"))
      (node (ref "R4") (pin "1") (pinfunction "1_1") (pintype "passive"))
    )
    (net (code "26") (name "Net-(D8-PadA)") (class "Default")
      (node (ref "D8") (pin "A") (pinfunction "A_A") (pintype "passive"))
      (node (ref "R11") (pin "1") (pinfunction "1_1") (pintype "passive"))
    )
    (net (code "27") (name "Net-(F1-Pad1)") (class "Default")
      (node (ref "F1") (pin "1") (pinfunction "1_1") (pintype "bidirectional"))
      (node (ref "USB1") (pin "1") (pinfunction "1_1") (pintype "input"))
    )
    (net (code "28") (name "Net-(IC3-D+)") (class "Default")
      (node (ref "IC3") (pin "4") (pinfunction "D+_4") (pintype "bidirectional"))
      (node (ref "USB1") (pin "3") (pinfunction "3_3") (pintype "input"))
    )
    (net (code "29") (name "Net-(IC3-D-)") (class "Default")
      (node (ref "IC3") (pin "5") (pinfunction "D-_5") (pintype "bidirectional"))
      (node (ref "USB1") (pin "2") (pinfunction "2_2") (pintype "input"))
    )
    (net (code "30") (name "Net-(IC3-DTR)") (class "Default")
      (node (ref "IC3") (pin "28") (pinfunction "DTR_28") (pintype "output"))
      (node (ref "Q2") (pin "2") (pinfunction "E_2") (pintype "passive"))
      (node (ref "R6") (pin "1") (pinfunction "1_1") (pintype "passive"))
    )
    (net (code "31") (name "Net-(IC3-RTS)") (class "Default")
      (node (ref "IC3") (pin "24") (pinfunction "RTS_24") (pintype "output"))
      (node (ref "Q1") (pin "2") (pinfunction "E_2") (pintype "passive"))
      (node (ref "R5") (pin "1") (pinfunction "1_1") (pintype "passive"))
    )
    (net (code "32") (name "Net-(IC3-~{RST})") (class "Default")
      (node (ref "IC3") (pin "9") (pinfunction "~{RST}_9") (pintype "bidirectional"))
      (node (ref "R3") (pin "2") (pinfunction "2_2") (pintype "passive"))
    )
    (net (code "33") (name "Net-(IC4-CLK)") (class "Default")
      (node (ref "IC4") (pin "20") (pinfunction "CLK_20") (pintype "bidirectional"))
      (node (ref "JP2") (pin "5") (pinfunction "5_5") (pintype "passive"))
    )
    (net (code "34") (name "Net-(IC4-CND)") (class "Default")
      (node (ref "IC4") (pin "19") (pinfunction "CND_19") (pintype "bidirectional"))
      (node (ref "JP2") (pin "6") (pinfunction "6_6") (pintype "passive"))
    )
    (net (code "35") (name "Net-(IC4-IO5)") (class "Default")
      (node (ref "IC4") (pin "29") (pinfunction "IO5_29") (pintype "bidirectional"))
      (node (ref "JP1") (pin "10") (pinfunction "10_10") (pintype "passive"))
      (node (ref "SJ6") (pin "1") (pinfunction "1_1") (pintype "passive"))
    )
    (net (code "36") (name "Net-(IC4-IO17)") (class "Default")
      (node (ref "IC4") (pin "28") (pinfunction "IO17_28") (pintype "bidirectional"))
      (node (ref "JP1") (pin "11") (pinfunction "11_11") (pintype "passive"))
      (node (ref "SJ7") (pin "1") (pinfunction "1_1") (pintype "passive"))
    )
    (net (code "37") (name "Net-(IC4-IO18)") (class "Default")
      (node (ref "IC4") (pin "30") (pinfunction "IO18_30") (pintype "bidirectional"))
      (node (ref "JP1") (pin "9") (pinfunction "9_9") (pintype "passive"))
      (node (ref "SJ5") (pin "1") (pinfunction "1_1") (pintype "passive"))
    )
    (net (code "38") (name "Net-(IC4-IO19)") (class "Default")
      (node (ref "IC4") (pin "31") (pinfunction "IO19_31") (pintype "bidirectional"))
      (node (ref "JP1") (pin "8") (pinfunction "8_8") (pintype "passive"))
      (node (ref "SJ4") (pin "1") (pinfunction "1_1") (pintype "passive"))
    )
    (net (code "39") (name "Net-(IC4-IO20)") (class "Default")
      (node (ref "IC4") (pin "32") (pinfunction "IO20_32") (pintype "bidirectional"))
      (node (ref "JP1") (pin "7") (pinfunction "7_7") (pintype "passive"))
      (node (ref "SJ3") (pin "1") (pinfunction "1_1") (pintype "passive"))
    )
    (net (code "40") (name "Net-(IC4-IO21)") (class "Default")
      (node (ref "IC4") (pin "33") (pinfunction "IO21_33") (pintype "bidirectional"))
      (node (ref "JP1") (pin "6") (pinfunction "6_6") (pintype "passive"))
      (node (ref "SJ2") (pin "1") (pinfunction "1_1") (pintype "passive"))
    )
    (net (code "41") (name "Net-(IC4-IO22)") (class "Default")
      (node (ref "IC4") (pin "36") (pinfunction "IO22_36") (pintype "bidirectional"))
      (node (ref "JP1") (pin "3") (pinfunction "3_3") (pintype "passive"))
      (node (ref "SJ1") (pin "1") (pinfunction "1_1") (pintype "passive"))
    )
    (net (code "42") (name "Net-(IC4-IO23)") (class "Default")
      (node (ref "IC4") (pin "37") (pinfunction "IO23_37") (pintype "bidirectional"))
      (node (ref "JP1") (pin "2") (pinfunction "2_2") (pintype "passive"))
    )
    (net (code "43") (name "Net-(IC4-IO25)") (class "Default")
      (node (ref "IC4") (pin "10") (pinfunction "IO25_10") (pintype "bidirectional"))
      (node (ref "JP3") (pin "5") (pinfunction "5_5") (pintype "passive"))
      (node (ref "SJ11") (pin "2") (pinfunction "2_2") (pintype "passive"))
    )
    (net (code "44") (name "Net-(IC4-IO26)") (class "Default")
      (node (ref "IC4") (pin "11") (pinfunction "IO26_11") (pintype "bidirectional"))
      (node (ref "JP3") (pin "4") (pinfunction "4_4") (pintype "passive"))
      (node (ref "SJ12") (pin "2") (pinfunction "2_2") (pintype "passive"))
    )
    (net (code "45") (name "Net-(IC4-IO27)") (class "Default")
      (node (ref "IC4") (pin "12") (pinfunction "IO27_12") (pintype "bidirectional"))
      (node (ref "JP3") (pin "3") (pinfunction "3_3") (pintype "passive"))
      (node (ref "SJ13") (pin "2") (pinfunction "2_2") (pintype "passive"))
    )
    (net (code "46") (name "Net-(IC4-IO32)") (class "Default")
      (node (ref "IC4") (pin "8") (pinfunction "IO32_8") (pintype "bidirectional"))
      (node (ref "JP3") (pin "7") (pinfunction "7_7") (pintype "passive"))
      (node (ref "SJ9") (pin "2") (pinfunction "2_2") (pintype "passive"))
    )
    (net (code "47") (name "Net-(IC4-IO33)") (class "Default")
      (node (ref "IC4") (pin "9") (pinfunction "IO33_9") (pintype "bidirectional"))
      (node (ref "JP3") (pin "6") (pinfunction "6_6") (pintype "passive"))
      (node (ref "SJ10") (pin "2") (pinfunction "2_2") (pintype "passive"))
    )
    (net (code "48") (name "Net-(IC4-IO34)") (class "Default")
      (node (ref "IC4") (pin "6") (pinfunction "IO34_6") (pintype "bidirectional"))
      (node (ref "JP3") (pin "9") (pinfunction "9_9") (pintype "passive"))
    )
    (net (code "49") (name "Net-(IC4-IO35)") (class "Default")
      (node (ref "IC4") (pin "7") (pinfunction "IO35_7") (pintype "bidirectional"))
      (node (ref "JP3") (pin "8") (pinfunction "8_8") (pintype "passive"))
      (node (ref "SJ8") (pin "2") (pinfunction "2_2") (pintype "passive"))
    )
    (net (code "50") (name "Net-(IC4-SD0)") (class "Default")
      (node (ref "IC4") (pin "21") (pinfunction "SD0_21") (pintype "bidirectional"))
      (node (ref "JP2") (pin "4") (pinfunction "4_4") (pintype "passive"))
    )
    (net (code "51") (name "Net-(IC4-SD1)") (class "Default")
      (node (ref "IC4") (pin "22") (pinfunction "SD1_22") (pintype "bidirectional"))
      (node (ref "JP2") (pin "3") (pinfunction "3_3") (pintype "passive"))
    )
    (net (code "52") (name "Net-(IC4-SD2)") (class "Default")
      (node (ref "IC4") (pin "17") (pinfunction "SD2_17") (pintype "bidirectional"))
      (node (ref "JP2") (pin "8") (pinfunction "8_8") (pintype "passive"))
    )
    (net (code "53") (name "Net-(IC4-SD3)") (class "Default")
      (node (ref "IC4") (pin "18") (pinfunction "SD3_18") (pintype "bidirectional"))
      (node (ref "JP2") (pin "7") (pinfunction "7_7") (pintype "passive"))
    )
    (net (code "54") (name "Net-(IC4-SENSOR_VN)") (class "Default")
      (node (ref "C21") (pin "2") (pinfunction "2_2") (pintype "passive"))
      (node (ref "IC4") (pin "5") (pinfunction "SENSOR_VN_5") (pintype "bidirectional"))
      (node (ref "JP3") (pin "10") (pinfunction "10_10") (pintype "passive"))
    )
    (net (code "55") (name "Net-(IC4-SENSOR_VP)") (class "Default")
      (node (ref "C20") (pin "2") (pinfunction "2_2") (pintype "passive"))
      (node (ref "IC4") (pin "4") (pinfunction "SENSOR_VP_4") (pintype "bidirectional"))
      (node (ref "JP3") (pin "11") (pinfunction "11_11") (pintype "passive"))
    )
    (net (code "56") (name "Net-(Q1-B)") (class "Default")
      (node (ref "Q1") (pin "1") (pinfunction "B_1") (pintype "passive"))
      (node (ref "R6") (pin "2") (pinfunction "2_2") (pintype "passive"))
    )
    (net (code "57") (name "Net-(Q2-B)") (class "Default")
      (node (ref "Q2") (pin "1") (pinfunction "B_1") (pintype "passive"))
      (node (ref "R5") (pin "2") (pinfunction "2_2") (pintype "passive"))
    )
    (net (code "58") (name "Net-(Q3-D)") (class "Default")
      (node (ref "C14") (pin "2") (pinfunction "2_2") (pintype "passive"))
      (node (ref "D7") (pin "A") (pinfunction "A_A") (pintype "passive"))
      (node (ref "L1") (pin "2") (pinfunction "2_2") (pintype "passive"))
      (node (ref "Q3") (pin "3") (pinfunction "D_3") (pintype "passive"))
    )
    (net (code "59") (name "PREVGH") (class "Default")
      (node (ref "C13") (pin "2") (pinfunction "2_2") (pintype "passive"))
      (node (ref "D7") (pin "C") (pinfunction "C_C") (pintype "passive"))
      (node (ref "J1") (pin "4") (pinfunction "4_4") (pintype "passive"))
    )
    (net (code "60") (name "PREVGL") (class "Default")
      (node (ref "C9") (pin "2") (pinfunction "2_2") (pintype "passive"))
      (node (ref "D2") (pin "A") (pinfunction "A_A") (pintype "passive"))
      (node (ref "J1") (pin "2") (pinfunction "2_2") (pintype "passive"))
    )
    (net (code "61") (name "RESE") (class "Default")
      (node (ref "J1") (pin "22") (pinfunction "22_22") (pintype "passive"))
      (node (ref "Q3") (pin "2") (pinfunction "S_2") (pintype "passive"))
      (node (ref "R7") (pin "1") (pinfunction "1_1") (pintype "passive"))
    )
    (net (code "62") (name "SD_CD") (class "Default")
      (node (ref "IC4") (pin "27") (pinfunction "IO16_27") (pintype "bidirectional"))
      (node (ref "JP1") (pin "12") (pinfunction "12_12") (pintype "passive"))
      (node (ref "R10") (pin "2") (pinfunction "2_2") (pintype "passive"))
      (node (ref "X701") (pin "CD1") (pinfunction "SHIELD_CD1") (pintype "bidirectional"))
    )
    (net (code "63") (name "SD_CLK") (class "Default")
      (node (ref "IC4") (pin "13") (pinfunction "IO14_13") (pintype "bidirectional"))
      (node (ref "JP3") (pin "2") (pinfunction "2_2") (pintype "passive"))
      (node (ref "X701") (pin "5") (pinfunction "SCK_5") (pintype "bidirectional"))
    )
    (net (code "64") (name "SD_CMD") (class "Default")
      (node (ref "IC4") (pin "23") (pinfunction "IO15_23") (pintype "bidirectional"))
      (node (ref "JP2") (pin "2") (pinfunction "2_2") (pintype "passive"))
      (node (ref "X701") (pin "3") (pinfunction "DI_3") (pintype "bidirectional"))
    )
    (net (code "65") (name "SD_DATA0") (class "Default")
      (node (ref "IC4") (pin "24") (pinfunction "IO2_24") (pintype "bidirectional"))
      (node (ref "JP2") (pin "1") (pinfunction "1_1") (pintype "passive"))
      (node (ref "X701") (pin "7") (pinfunction "DO_7") (pintype "bidirectional"))
    )
    (net (code "66") (name "SD_DATA1") (class "Default")
      (node (ref "IC4") (pin "26") (pinfunction "IO4_26") (pintype "bidirectional"))
      (node (ref "JP1") (pin "13") (pinfunction "13_13") (pintype "passive"))
      (node (ref "X701") (pin "8") (pinfunction "RSV_8") (pintype "bidirectional"))
    )
    (net (code "67") (name "SD_DATA2") (class "Default")
      (node (ref "IC4") (pin "14") (pinfunction "IO12_14") (pintype "bidirectional"))
      (node (ref "JP3") (pin "1") (pinfunction "1_1") (pintype "passive"))
      (node (ref "X701") (pin "1") (pinfunction "NC_1") (pintype "bidirectional"))
    )
    (net (code "68") (name "SD_DATA3") (class "Default")
      (node (ref "IC4") (pin "16") (pinfunction "IO13_16") (pintype "bidirectional"))
      (node (ref "JP2") (pin "9") (pinfunction "9_9") (pintype "passive"))
      (node (ref "X701") (pin "2") (pinfunction "CS_2") (pintype "bidirectional"))
    )
    (net (code "69") (name "TSCL") (class "Default")
      (node (ref "J1") (pin "19") (pinfunction "19_19") (pintype "passive"))
    )
    (net (code "70") (name "TSDA") (class "Default")
      (node (ref "J1") (pin "18") (pinfunction "18_18") (pintype "passive"))
    )
    (net (code "71") (name "VCOM") (class "Default")
      (node (ref "C7") (pin "2") (pinfunction "2_2") (pintype "passive"))
      (node (ref "J1") (pin "1") (pinfunction "1_1") (pintype "passive"))
    )
    (net (code "72") (name "VDD") (class "Default")
      (node (ref "C6") (pin "1") (pinfunction "1_1") (pintype "passive"))
      (node (ref "IC3") (pin "6") (pinfunction "VDD_6") (pintype "power_in"))
      (node (ref "R1") (pin "2") (pinfunction "2_2") (pintype "passive"))
      (node (ref "R2") (pin "2") (pinfunction "2_2") (pintype "passive"))
      (node (ref "R3") (pin "1") (pinfunction "1_1") (pintype "passive"))
      (node (ref "R4") (pin "2") (pinfunction "2_2") (pintype "passive"))
    )
    (net (code "73") (name "VGH") (class "Default")
      (node (ref "C17") (pin "2") (pinfunction "2_2") (pintype "passive"))
      (node (ref "J1") (pin "20") (pinfunction "20_20") (pintype "passive"))
    )
    (net (code "74") (name "VGL") (class "Default")
      (node (ref "C18") (pin "2") (pinfunction "2_2") (pintype "passive"))
      (node (ref "J1") (pin "21") (pinfunction "21_21") (pintype "passive"))
    )
    (net (code "75") (name "VPP") (class "Default")
      (node (ref "J1") (pin "6") (pinfunction "6_6") (pintype "passive"))
    )
    (net (code "76") (name "VSH") (class "Default")
      (node (ref "C12") (pin "2") (pinfunction "2_2") (pintype "passive"))
      (node (ref "J1") (pin "5") (pinfunction "5_5") (pintype "passive"))
    )
    (net (code "77") (name "VSL") (class "Default")
      (node (ref "C10") (pin "2") (pinfunction "2_2") (pintype "passive"))
      (node (ref "J1") (pin "3") (pinfunction "3_3") (pintype "passive"))
    )
    (net (code "78") (name "unconnected-(IC3-CTS-Pad23)") (class "Default")
      (node (ref "IC3") (pin "23") (pinfunction "CTS_23") (pintype "input"))
    )
    (net (code "79") (name "unconnected-(IC3-DCD-Pad1)") (class "Default")
      (node (ref "IC3") (pin "1") (pinfunction "DCD_1") (pintype "input"))
    )
    (net (code "80") (name "unconnected-(IC3-DSR-Pad27)") (class "Default")
      (node (ref "IC3") (pin "27") (pinfunction "DSR_27") (pintype "input"))
    )
    (net (code "81") (name "unconnected-(IC3-RI-Pad2)") (class "Default")
      (node (ref "IC3") (pin "2") (pinfunction "RI_2") (pintype "input"))
    )
    (net (code "82") (name "unconnected-(IC3-SUSPEND-Pad12)") (class "Default")
      (node (ref "IC3") (pin "12") (pinfunction "SUSPEND_12") (pintype "output"))
    )
    (net (code "83") (name "unconnected-(IC3-~{SUSPEND}-Pad11)") (class "Default")
      (node (ref "IC3") (pin "11") (pinfunction "~{SUSPEND}_11") (pintype "output"))
    )
    (net (code "84") (name "unconnected-(J1-Pad24)") (class "Default")
      (node (ref "J1") (pin "24") (pinfunction "24_24") (pintype "passive"))
    )
    (net (code "85") (name "unconnected-(USB1-Pad4)") (class "Default")
      (node (ref "USB1") (pin "4") (pinfunction "4_4") (pintype "input"))
    )
  )
)
